# finalschematic.net
KiCad netlist of a schematic drawn in EAGLE
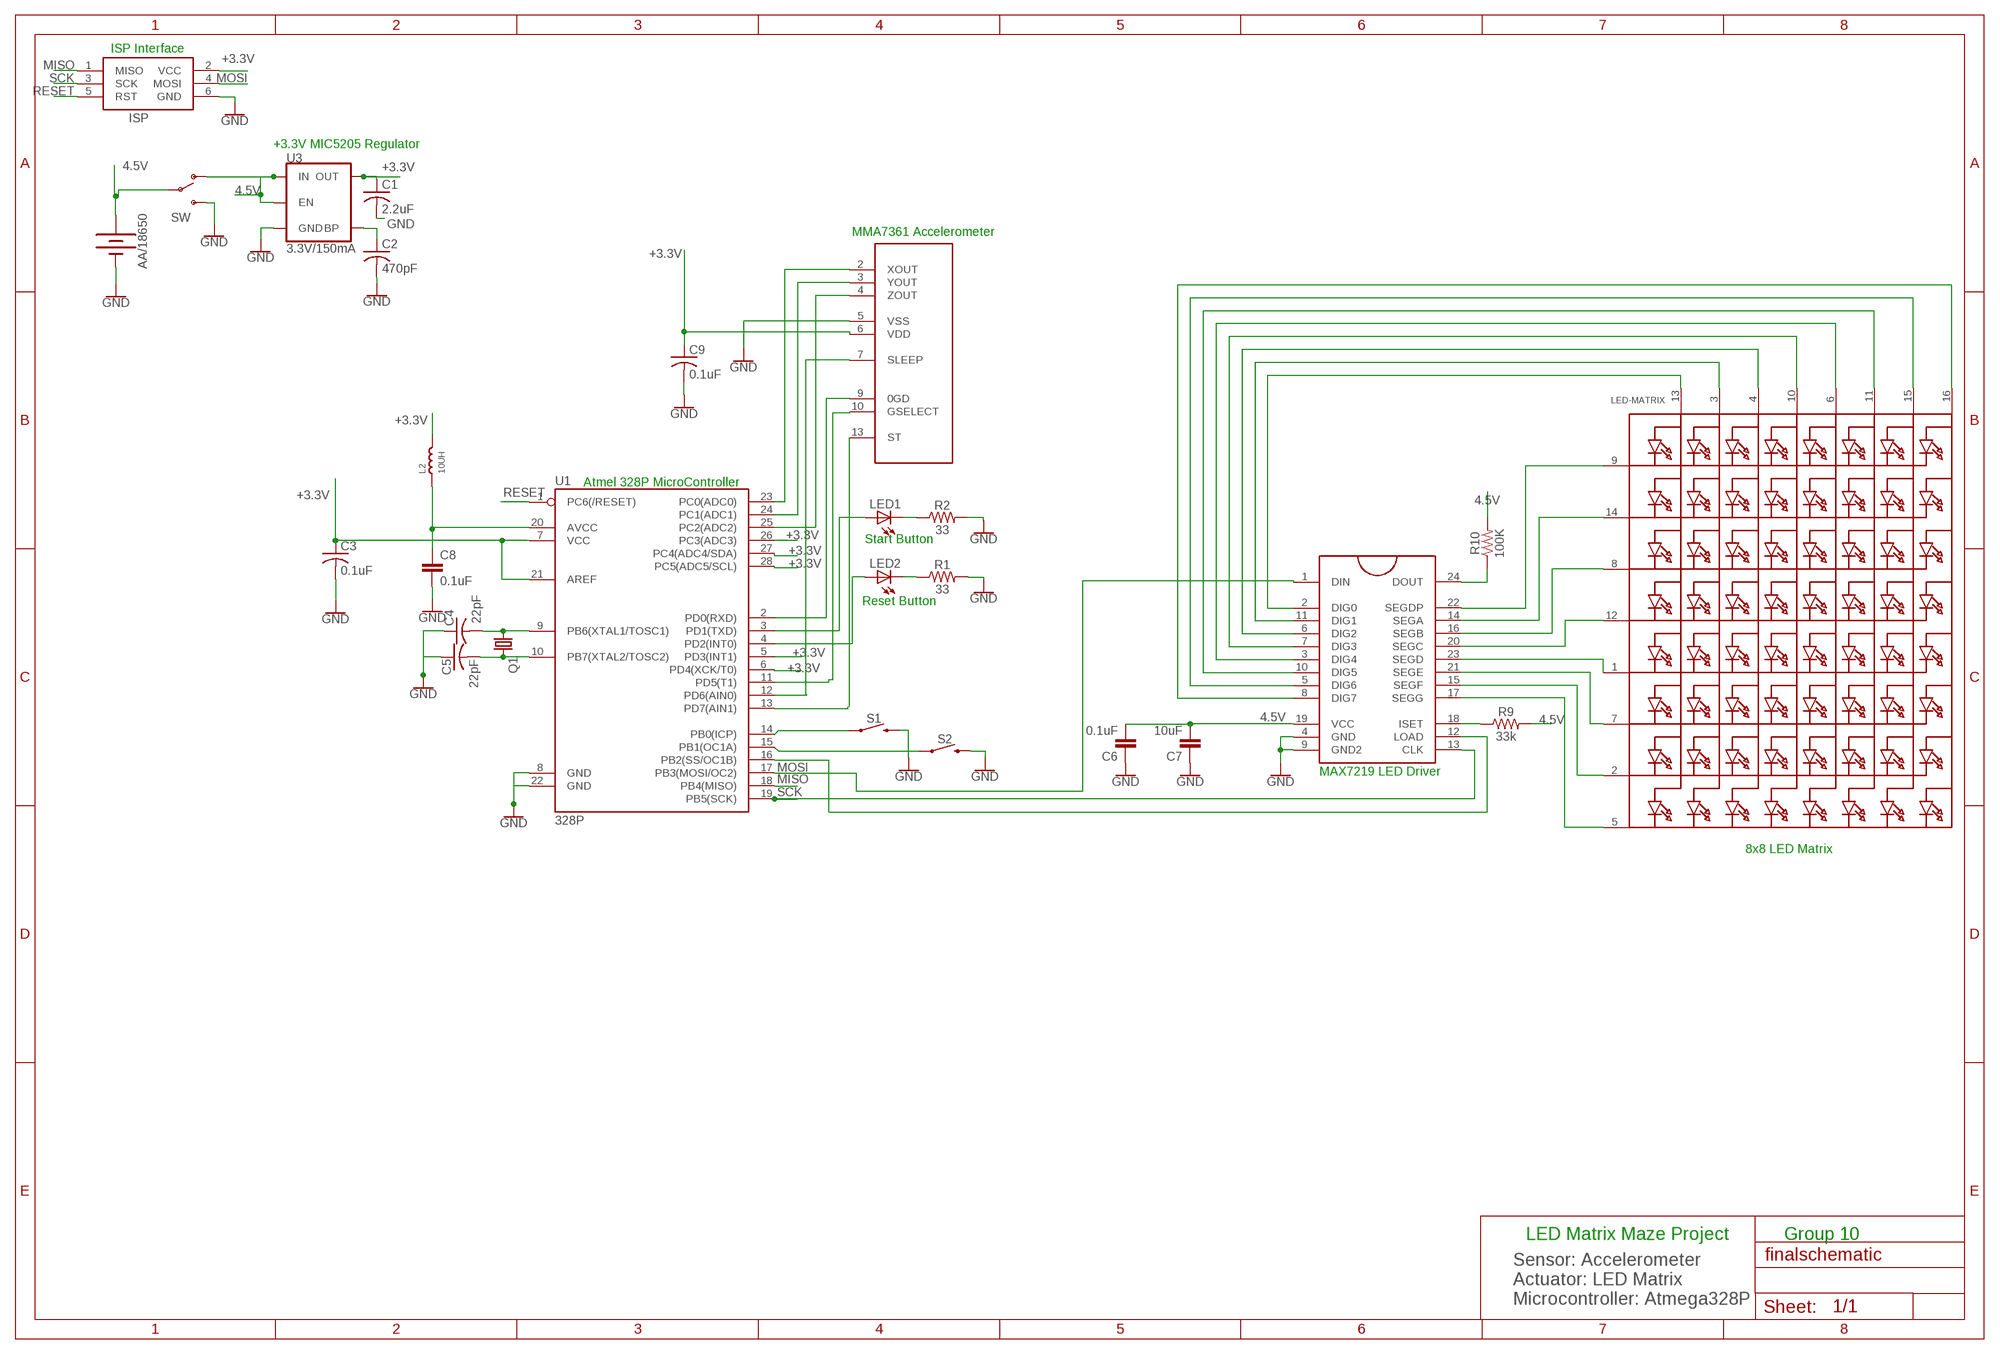
[diagram p0: schematic, sheet 1]

(export (version "E")
  (design (tool "Eeschema 10.0.6"))
  (components
    (comp (ref "AA/18650")
      (value "BATTERY-9V")
      (footprint "eagle-import:BATTCON_9V")
      (libsource (lib "eagle-import") (part "BATTERY-9V"))
    )
    (comp (ref "C1")
      (value "2.2uF")
      (footprint "eagle-import:C025-024X044")
      (libsource (lib "eagle-import") (part "C-US025-024X044"))
    )
    (comp (ref "C2")
      (value "470pF")
      (footprint "eagle-import:C025-024X044")
      (libsource (lib "eagle-import") (part "C-US025-024X044"))
    )
    (comp (ref "C3")
      (value "0.1uF")
      (footprint "eagle-import:C025-024X044")
      (libsource (lib "eagle-import") (part "C-US025-024X044"))
    )
    (comp (ref "C4")
      (value "22pF")
      (footprint "eagle-import:C025-024X044")
      (libsource (lib "eagle-import") (part "C-US025-024X044"))
    )
    (comp (ref "C5")
      (value "22pF")
      (footprint "eagle-import:C025-024X044")
      (libsource (lib "eagle-import") (part "C-US025-024X044"))
    )
    (comp (ref "C6")
      (value "0.1uF")
      (footprint "eagle-import:0603")
      (libsource (lib "eagle-import") (part "0.1UF-0603-25V-5%"))
    )
    (comp (ref "C7")
      (value "10uF")
      (footprint "eagle-import:0603")
      (libsource (lib "eagle-import") (part "10UF-0603-6.3V-20%"))
    )
    (comp (ref "C8")
      (value "0.1uF")
      (footprint "eagle-import:0603")
      (libsource (lib "eagle-import") (part "0.1UF-0603-25V-5%"))
    )
    (comp (ref "C9")
      (value "0.1uF")
      (footprint "eagle-import:C025-024X044")
      (libsource (lib "eagle-import") (part "C-US025-024X044"))
    )
    (comp (ref "ISP")
      (value "AVRISP-6")
      (footprint "eagle-import:AVRISP")
      (libsource (lib "eagle-import") (part "AVRISP-6"))
    )
    (comp (ref "L2")
      (value "10UH")
      (footprint "eagle-import:SMD-2P-L6.0XW6.0XH3.0MM")
      (fields (field (name "MPN") "CSAB0630-100M"))
      (libsource (lib "eagle-import") (part "SMD-INDUCTOR-10UH-20%(2P-6X6MM)'0630'"))
    )
    (comp (ref "LED-MATRIX")
      (value "SEGMENT_8X8_ROWCATHODEM12A881UR")
      (footprint "eagle-import:SEGMENT_BL-M12A881UR")
      (libsource (lib "eagle-import") (part "SEGMENT_8X8_ROWCATHODEM12A881UR"))
    )
    (comp (ref "LED1")
      (value "LED")
      (footprint "eagle-import:SMARTLED-TTW")
      (libsource (lib "eagle-import") (part "LED"))
    )
    (comp (ref "LED2")
      (value "LED")
      (footprint "eagle-import:SMARTLED-TTW")
      (libsource (lib "eagle-import") (part "LED"))
    )
    (comp (ref "Q1")
      (value "CRYSTALHC49S")
      (footprint "eagle-import:HC49_S")
      (libsource (lib "eagle-import") (part "CRYSTALHC49S"))
    )
    (comp (ref "R1")
      (value "33")
      (footprint "eagle-import:0603")
      (libsource (lib "eagle-import") (part "33OHM-0603-1/10W-1%"))
    )
    (comp (ref "R2")
      (value "33")
      (footprint "eagle-import:0603")
      (libsource (lib "eagle-import") (part "33OHM-0603-1/10W-1%"))
    )
    (comp (ref "R9")
      (value "33k")
      (footprint "eagle-import:0603")
      (libsource (lib "eagle-import") (part "33KOHM-0603-1/10W-1%"))
    )
    (comp (ref "R10")
      (value "100K")
      (footprint "eagle-import:0402")
      (libsource (lib "eagle-import") (part "100KOHM-0402-1/16W-1%"))
    )
    (comp (ref "S1")
      (value "MOMENTARY-SWITCH-SPST-SMD-6.0X3.5MM")
      (footprint "eagle-import:TACTILE_SWITCH_SMD_6.0X3.5MM")
      (libsource (lib "eagle-import") (part "MOMENTARY-SWITCH-SPST-SMD-6.0X3.5MM"))
    )
    (comp (ref "S2")
      (value "MOMENTARY-SWITCH-SPST-SMD-6.0X3.5MM")
      (footprint "eagle-import:TACTILE_SWITCH_SMD_6.0X3.5MM")
      (libsource (lib "eagle-import") (part "MOMENTARY-SWITCH-SPST-SMD-6.0X3.5MM"))
    )
    (comp (ref "SW")
      (value "SWITCH-SPSTPTH_LOCK")
      (footprint "eagle-import:SWITCH-SPDT_LOCK.007S")
      (libsource (lib "eagle-import") (part "SWITCH-SPSTPTH_LOCK"))
    )
    (comp (ref "U$1")
      (value "MAX7219DIP")
      (footprint "eagle-import:DIL24")
      (libsource (lib "eagle-import") (part "MAX7219DIP"))
    )
    (comp (ref "U$2")
      (value "MMA7361")
      (footprint "eagle-import:LGA14")
      (libsource (lib "eagle-import") (part "MMA7361"))
    )
    (comp (ref "U1")
      (value "328P")
      (footprint "eagle-import:DIP28")
      (libsource (lib "eagle-import") (part "ATMEGA328P_PDIP"))
    )
    (comp (ref "U3")
      (value "3.3V/150mA")
      (footprint "eagle-import:SOT23-5")
      (libsource (lib "eagle-import") (part "V_REG_MIC52053.3V"))
    )
  )
  (nets
    (net (code "1") (name "/+3.3V") (class "Default")
      (node (ref "C1") (pin "1") (pinfunction "1_1") (pintype "passive"))
      (node (ref "C3") (pin "1") (pinfunction "1_1") (pintype "passive"))
      (node (ref "C9") (pin "1") (pinfunction "1_1") (pintype "passive"))
      (node (ref "ISP") (pin "2") (pinfunction "VCC_2") (pintype "power_in"))
      (node (ref "L2") (pin "2") (pinfunction "2_2") (pintype "passive"))
      (node (ref "U$2") (pin "6") (pinfunction "VDD_6") (pintype "bidirectional"))
      (node (ref "U1") (pin "21") (pinfunction "AREF_21") (pintype "bidirectional"))
      (node (ref "U1") (pin "26") (pinfunction "PC3(ADC3)_26") (pintype "bidirectional"))
      (node (ref "U1") (pin "27") (pinfunction "PC4(ADC4/SDA)_27") (pintype "bidirectional"))
      (node (ref "U1") (pin "28") (pinfunction "PC5(ADC5/SCL)_28") (pintype "bidirectional"))
      (node (ref "U1") (pin "5") (pinfunction "PD3(INT1)_5") (pintype "bidirectional"))
      (node (ref "U1") (pin "6") (pinfunction "PD4(XCK/T0)_6") (pintype "bidirectional"))
      (node (ref "U1") (pin "7") (pinfunction "VCC_7") (pintype "bidirectional"))
      (node (ref "U3") (pin "5") (pinfunction "OUT_5") (pintype "passive"))
    )
    (net (code "2") (name "/4.5V") (class "Default")
      (node (ref "AA/18650") (pin "+") (pinfunction "+_+") (pintype "power_in"))
      (node (ref "C6") (pin "2") (pinfunction "2_2") (pintype "passive"))
      (node (ref "C7") (pin "2") (pinfunction "2_2") (pintype "passive"))
      (node (ref "R10") (pin "2") (pinfunction "2_2") (pintype "passive"))
      (node (ref "R9") (pin "2") (pinfunction "2_2") (pintype "passive"))
      (node (ref "SW") (pin "1") (pinfunction "O_1") (pintype "passive"))
      (node (ref "SW") (pin "2") (pinfunction "P_2") (pintype "passive"))
      (node (ref "U$1") (pin "19") (pinfunction "VCC_19") (pintype "bidirectional"))
      (node (ref "U3") (pin "1") (pinfunction "IN_1") (pintype "input"))
      (node (ref "U3") (pin "3") (pinfunction "EN_3") (pintype "input"))
    )
    (net (code "3") (name "/MISO") (class "Default")
      (node (ref "ISP") (pin "1") (pinfunction "MISO_1") (pintype "input"))
      (node (ref "U1") (pin "18") (pinfunction "PB4(MISO)_18") (pintype "bidirectional"))
    )
    (net (code "4") (name "/MOSI") (class "Default")
      (node (ref "ISP") (pin "4") (pinfunction "MOSI_4") (pintype "output"))
      (node (ref "U$1") (pin "1") (pinfunction "DIN_1") (pintype "bidirectional"))
      (node (ref "U1") (pin "17") (pinfunction "PB3(MOSI/OC2)_17") (pintype "bidirectional"))
    )
    (net (code "5") (name "/RESET") (class "Default")
      (node (ref "ISP") (pin "5") (pinfunction "RST_5") (pintype "output"))
      (node (ref "U1") (pin "1") (pinfunction "PC6(/RESET)_1") (pintype "bidirectional"))
    )
    (net (code "6") (name "/SCK") (class "Default")
      (node (ref "ISP") (pin "3") (pinfunction "SCK_3") (pintype "output"))
      (node (ref "U$1") (pin "13") (pinfunction "CLK_13") (pintype "bidirectional"))
      (node (ref "U1") (pin "19") (pinfunction "PB5(SCK)_19") (pintype "bidirectional"))
    )
    (net (code "7") (name "GND") (class "Default")
      (node (ref "AA/18650") (pin "-") (pinfunction "-_-") (pintype "power_in"))
      (node (ref "C1") (pin "2") (pinfunction "2_2") (pintype "passive"))
      (node (ref "C2") (pin "2") (pinfunction "2_2") (pintype "passive"))
      (node (ref "C3") (pin "2") (pinfunction "2_2") (pintype "passive"))
      (node (ref "C4") (pin "1") (pinfunction "1_1") (pintype "passive"))
      (node (ref "C5") (pin "1") (pinfunction "1_1") (pintype "passive"))
      (node (ref "C6") (pin "1") (pinfunction "1_1") (pintype "passive"))
      (node (ref "C7") (pin "1") (pinfunction "1_1") (pintype "passive"))
      (node (ref "C8") (pin "2") (pinfunction "2_2") (pintype "passive"))
      (node (ref "C9") (pin "2") (pinfunction "2_2") (pintype "passive"))
      (node (ref "ISP") (pin "6") (pinfunction "GND_6") (pintype "power_in"))
      (node (ref "R1") (pin "2") (pinfunction "2_2") (pintype "passive"))
      (node (ref "R2") (pin "2") (pinfunction "2_2") (pintype "passive"))
      (node (ref "S1") (pin "2") (pinfunction "2_2") (pintype "passive"))
      (node (ref "S2") (pin "2") (pinfunction "2_2") (pintype "passive"))
      (node (ref "SW") (pin "3") (pinfunction "S_3") (pintype "passive"))
      (node (ref "U$1") (pin "4") (pinfunction "GND_4") (pintype "bidirectional"))
      (node (ref "U$1") (pin "9") (pinfunction "GND2_9") (pintype "bidirectional"))
      (node (ref "U$2") (pin "5") (pinfunction "VSS_5") (pintype "bidirectional"))
      (node (ref "U1") (pin "22") (pinfunction "GND_22") (pintype "bidirectional"))
      (node (ref "U1") (pin "8") (pinfunction "GND_8") (pintype "bidirectional"))
      (node (ref "U3") (pin "2") (pinfunction "GND_2") (pintype "input"))
    )
    (net (code "8") (name "Net-(LED-MATRIX-A1)") (class "Default")
      (node (ref "LED-MATRIX") (pin "13") (pinfunction "A1_13") (pintype "bidirectional"))
      (node (ref "U$1") (pin "2") (pinfunction "DIG0_2") (pintype "bidirectional"))
    )
    (net (code "9") (name "Net-(LED-MATRIX-A2)") (class "Default")
      (node (ref "LED-MATRIX") (pin "3") (pinfunction "A2_3") (pintype "bidirectional"))
      (node (ref "U$1") (pin "11") (pinfunction "DIG1_11") (pintype "bidirectional"))
    )
    (net (code "10") (name "Net-(LED-MATRIX-A3)") (class "Default")
      (node (ref "LED-MATRIX") (pin "4") (pinfunction "A3_4") (pintype "bidirectional"))
      (node (ref "U$1") (pin "6") (pinfunction "DIG2_6") (pintype "bidirectional"))
    )
    (net (code "11") (name "Net-(LED-MATRIX-A4)") (class "Default")
      (node (ref "LED-MATRIX") (pin "10") (pinfunction "A4_10") (pintype "bidirectional"))
      (node (ref "U$1") (pin "7") (pinfunction "DIG3_7") (pintype "bidirectional"))
    )
    (net (code "12") (name "Net-(LED-MATRIX-A5)") (class "Default")
      (node (ref "LED-MATRIX") (pin "6") (pinfunction "A5_6") (pintype "bidirectional"))
      (node (ref "U$1") (pin "3") (pinfunction "DIG4_3") (pintype "bidirectional"))
    )
    (net (code "13") (name "Net-(LED-MATRIX-A6)") (class "Default")
      (node (ref "LED-MATRIX") (pin "11") (pinfunction "A6_11") (pintype "bidirectional"))
      (node (ref "U$1") (pin "10") (pinfunction "DIG5_10") (pintype "bidirectional"))
    )
    (net (code "14") (name "Net-(LED-MATRIX-A7)") (class "Default")
      (node (ref "LED-MATRIX") (pin "15") (pinfunction "A7_15") (pintype "bidirectional"))
      (node (ref "U$1") (pin "5") (pinfunction "DIG6_5") (pintype "bidirectional"))
    )
    (net (code "15") (name "Net-(LED-MATRIX-A8)") (class "Default")
      (node (ref "LED-MATRIX") (pin "16") (pinfunction "A8_16") (pintype "bidirectional"))
      (node (ref "U$1") (pin "8") (pinfunction "DIG7_8") (pintype "bidirectional"))
    )
    (net (code "16") (name "Net-(LED-MATRIX-K1)") (class "Default")
      (node (ref "LED-MATRIX") (pin "9") (pinfunction "K1_9") (pintype "bidirectional"))
      (node (ref "U$1") (pin "22") (pinfunction "SEGDP_22") (pintype "bidirectional"))
    )
    (net (code "17") (name "Net-(LED-MATRIX-K2)") (class "Default")
      (node (ref "LED-MATRIX") (pin "14") (pinfunction "K2_14") (pintype "bidirectional"))
      (node (ref "U$1") (pin "14") (pinfunction "SEGA_14") (pintype "bidirectional"))
    )
    (net (code "18") (name "Net-(LED-MATRIX-K3)") (class "Default")
      (node (ref "LED-MATRIX") (pin "8") (pinfunction "K3_8") (pintype "bidirectional"))
      (node (ref "U$1") (pin "16") (pinfunction "SEGB_16") (pintype "bidirectional"))
    )
    (net (code "19") (name "Net-(LED-MATRIX-K4)") (class "Default")
      (node (ref "LED-MATRIX") (pin "12") (pinfunction "K4_12") (pintype "bidirectional"))
      (node (ref "U$1") (pin "20") (pinfunction "SEGC_20") (pintype "bidirectional"))
    )
    (net (code "20") (name "Net-(LED-MATRIX-K5)") (class "Default")
      (node (ref "LED-MATRIX") (pin "1") (pinfunction "K5_1") (pintype "bidirectional"))
      (node (ref "U$1") (pin "23") (pinfunction "SEGD_23") (pintype "bidirectional"))
    )
    (net (code "21") (name "Net-(LED-MATRIX-K6)") (class "Default")
      (node (ref "LED-MATRIX") (pin "7") (pinfunction "K6_7") (pintype "bidirectional"))
      (node (ref "U$1") (pin "21") (pinfunction "SEGE_21") (pintype "bidirectional"))
    )
    (net (code "22") (name "Net-(LED-MATRIX-K7)") (class "Default")
      (node (ref "LED-MATRIX") (pin "2") (pinfunction "K7_2") (pintype "bidirectional"))
      (node (ref "U$1") (pin "15") (pinfunction "SEGF_15") (pintype "bidirectional"))
    )
    (net (code "23") (name "Net-(LED-MATRIX-K8)") (class "Default")
      (node (ref "LED-MATRIX") (pin "5") (pinfunction "K8_5") (pintype "bidirectional"))
      (node (ref "U$1") (pin "17") (pinfunction "SEGG_17") (pintype "bidirectional"))
    )
    (net (code "24") (name "Net-(LED1-A)") (class "Default")
      (node (ref "LED1") (pin "A@1") (pinfunction "A_A@1") (pintype "passive"))
      (node (ref "U1") (pin "3") (pinfunction "PD1(TXD)_3") (pintype "bidirectional"))
    )
    (net (code "25") (name "Net-(LED1-C)") (class "Default")
      (node (ref "LED1") (pin "C@1") (pinfunction "C_C@1") (pintype "passive"))
      (node (ref "R2") (pin "1") (pinfunction "1_1") (pintype "passive"))
    )
    (net (code "26") (name "Net-(LED2-A)") (class "Default")
      (node (ref "LED2") (pin "A@1") (pinfunction "A_A@1") (pintype "passive"))
      (node (ref "U1") (pin "4") (pinfunction "PD2(INT0)_4") (pintype "bidirectional"))
    )
    (net (code "27") (name "Net-(LED2-C)") (class "Default")
      (node (ref "LED2") (pin "C@1") (pinfunction "C_C@1") (pintype "passive"))
      (node (ref "R1") (pin "1") (pinfunction "1_1") (pintype "passive"))
    )
    (net (code "28") (name "Net-(U$1-DOUT)") (class "Default")
      (node (ref "R10") (pin "1") (pinfunction "1_1") (pintype "passive"))
      (node (ref "U$1") (pin "24") (pinfunction "DOUT_24") (pintype "bidirectional"))
    )
    (net (code "29") (name "Net-(U$1-ISET)") (class "Default")
      (node (ref "R9") (pin "1") (pinfunction "1_1") (pintype "passive"))
      (node (ref "U$1") (pin "18") (pinfunction "ISET_18") (pintype "bidirectional"))
    )
    (net (code "30") (name "Net-(U$1-LOAD)") (class "Default")
      (node (ref "U$1") (pin "12") (pinfunction "LOAD_12") (pintype "bidirectional"))
      (node (ref "U1") (pin "16") (pinfunction "PB2(SS/OC1B)_16") (pintype "bidirectional"))
    )
    (net (code "31") (name "Net-(U$2-0GD)") (class "Default")
      (node (ref "U$2") (pin "9") (pinfunction "0GD_9") (pintype "bidirectional"))
      (node (ref "U1") (pin "2") (pinfunction "PD0(RXD)_2") (pintype "bidirectional"))
    )
    (net (code "32") (name "Net-(U$2-GSELECT)") (class "Default")
      (node (ref "U$2") (pin "10") (pinfunction "GSELECT_10") (pintype "bidirectional"))
      (node (ref "U1") (pin "11") (pinfunction "PD5(T1)_11") (pintype "bidirectional"))
    )
    (net (code "33") (name "Net-(U$2-SLEEP)") (class "Default")
      (node (ref "U$2") (pin "7") (pinfunction "SLEEP_7") (pintype "bidirectional"))
      (node (ref "U1") (pin "12") (pinfunction "PD6(AIN0)_12") (pintype "bidirectional"))
    )
    (net (code "34") (name "Net-(U$2-ST)") (class "Default")
      (node (ref "U$2") (pin "13") (pinfunction "ST_13") (pintype "bidirectional"))
      (node (ref "U1") (pin "13") (pinfunction "PD7(AIN1)_13") (pintype "bidirectional"))
    )
    (net (code "35") (name "Net-(U$2-XOUT)") (class "Default")
      (node (ref "U$2") (pin "2") (pinfunction "XOUT_2") (pintype "bidirectional"))
      (node (ref "U1") (pin "23") (pinfunction "PC0(ADC0)_23") (pintype "bidirectional"))
    )
    (net (code "36") (name "Net-(U$2-YOUT)") (class "Default")
      (node (ref "U$2") (pin "3") (pinfunction "YOUT_3") (pintype "bidirectional"))
      (node (ref "U1") (pin "24") (pinfunction "PC1(ADC1)_24") (pintype "bidirectional"))
    )
    (net (code "37") (name "Net-(U$2-ZOUT)") (class "Default")
      (node (ref "U$2") (pin "4") (pinfunction "ZOUT_4") (pintype "bidirectional"))
      (node (ref "U1") (pin "25") (pinfunction "PC2(ADC2)_25") (pintype "bidirectional"))
    )
    (net (code "38") (name "Net-(U1-AVCC)") (class "Default")
      (node (ref "C8") (pin "1") (pinfunction "1_1") (pintype "passive"))
      (node (ref "L2") (pin "1") (pinfunction "1_1") (pintype "passive"))
      (node (ref "U1") (pin "20") (pinfunction "AVCC_20") (pintype "bidirectional"))
    )
    (net (code "39") (name "Net-(U1-PB0(ICP))") (class "Default")
      (node (ref "S1") (pin "1") (pinfunction "1_1") (pintype "passive"))
      (node (ref "U1") (pin "14") (pinfunction "PB0(ICP)_14") (pintype "bidirectional"))
    )
    (net (code "40") (name "Net-(U1-PB1(OC1A))") (class "Default")
      (node (ref "S2") (pin "1") (pinfunction "1_1") (pintype "passive"))
      (node (ref "U1") (pin "15") (pinfunction "PB1(OC1A)_15") (pintype "bidirectional"))
    )
    (net (code "41") (name "Net-(U1-PB6(XTAL1{slash}TOSC1))") (class "Default")
      (node (ref "C4") (pin "2") (pinfunction "2_2") (pintype "passive"))
      (node (ref "Q1") (pin "1") (pinfunction "1_1") (pintype "passive"))
      (node (ref "U1") (pin "9") (pinfunction "PB6(XTAL1/TOSC1)_9") (pintype "bidirectional"))
    )
    (net (code "42") (name "Net-(U1-PB7(XTAL2{slash}TOSC2))") (class "Default")
      (node (ref "C5") (pin "2") (pinfunction "2_2") (pintype "passive"))
      (node (ref "Q1") (pin "2") (pinfunction "2_2") (pintype "passive"))
      (node (ref "U1") (pin "10") (pinfunction "PB7(XTAL2/TOSC2)_10") (pintype "bidirectional"))
    )
    (net (code "43") (name "Net-(U3-BP)") (class "Default")
      (node (ref "C2") (pin "1") (pinfunction "1_1") (pintype "passive"))
      (node (ref "U3") (pin "4") (pinfunction "BP_4") (pintype "input"))
    )
  )
)
